# Nucleo.net
KiCad netlist of a schematic drawn in Altium Designer
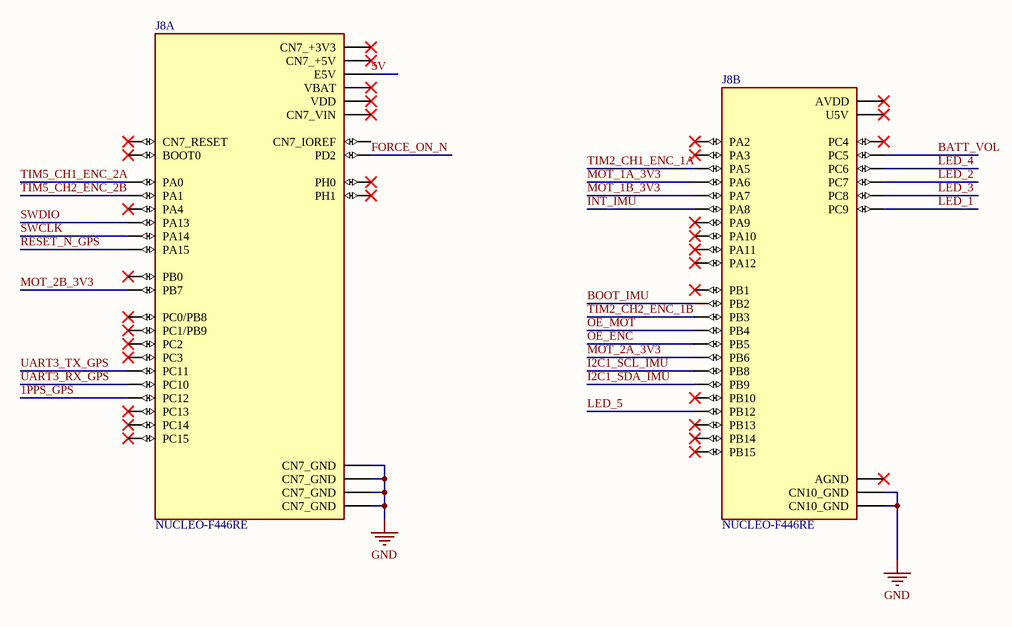
[diagram p0: Nucleo.SchDoc]

(export (version "E")
  (design (tool "Eeschema 10.0.6"))
  (components
    (comp (ref "J8")
      (value "NUCLEO-F446RE")
      (footprint "swarm_crawler_pcb:MODULE_NUCLEO-F446RE")
      (libsource (lib "swarm_crawler_sch") (part "NUCLEO-F446RE"))
    )
  )
  (nets
    (net (code "1") (name "/1PPS_GPS") (class "Default")
      (node (ref "J8") (pin "CN7_3") (pinfunction "PC12_CN7_3") (pintype "bidirectional"))
    )
    (net (code "2") (name "/5V") (class "Default")
      (node (ref "J8") (pin "CN7_6") (pinfunction "E5V_CN7_6") (pintype "power_in"))
    )
    (net (code "3") (name "/BATT_VOL") (class "Default")
      (node (ref "J8") (pin "CN10_6") (pinfunction "PC5_CN10_6") (pintype "bidirectional"))
    )
    (net (code "4") (name "/BOOT_IMU") (class "Default")
      (node (ref "J8") (pin "CN10_22") (pinfunction "PB2_CN10_22") (pintype "bidirectional"))
    )
    (net (code "5") (name "/FORCE_ON_N") (class "Default")
      (node (ref "J8") (pin "CN7_4") (pinfunction "PD2_CN7_4") (pintype "bidirectional"))
    )
    (net (code "6") (name "/I2C1_SCL_IMU") (class "Default")
      (node (ref "J8") (pin "CN10_3") (pinfunction "PB8_CN10_3") (pintype "bidirectional"))
    )
    (net (code "7") (name "/I2C1_SDA_IMU") (class "Default")
      (node (ref "J8") (pin "CN10_5") (pinfunction "PB9_CN10_5") (pintype "bidirectional"))
    )
    (net (code "8") (name "/INT_IMU") (class "Default")
      (node (ref "J8") (pin "CN10_23") (pinfunction "PA8_CN10_23") (pintype "bidirectional"))
    )
    (net (code "9") (name "/LED_1") (class "Default")
      (node (ref "J8") (pin "CN10_1") (pinfunction "PC9_CN10_1") (pintype "bidirectional"))
    )
    (net (code "10") (name "/LED_2") (class "Default")
      (node (ref "J8") (pin "CN10_19") (pinfunction "PC7_CN10_19") (pintype "bidirectional"))
    )
    (net (code "11") (name "/LED_3") (class "Default")
      (node (ref "J8") (pin "CN10_2") (pinfunction "PC8_CN10_2") (pintype "bidirectional"))
    )
    (net (code "12") (name "/LED_4") (class "Default")
      (node (ref "J8") (pin "CN10_4") (pinfunction "PC6_CN10_4") (pintype "bidirectional"))
    )
    (net (code "13") (name "/LED_5") (class "Default")
      (node (ref "J8") (pin "CN10_16") (pinfunction "PB12_CN10_16") (pintype "bidirectional"))
    )
    (net (code "14") (name "/MOT_1A_3V3") (class "Default")
      (node (ref "J8") (pin "CN10_13") (pinfunction "PA6_CN10_13") (pintype "bidirectional"))
    )
    (net (code "15") (name "/MOT_1B_3V3") (class "Default")
      (node (ref "J8") (pin "CN10_15") (pinfunction "PA7_CN10_15") (pintype "bidirectional"))
    )
    (net (code "16") (name "/MOT_2A_3V3") (class "Default")
      (node (ref "J8") (pin "CN10_17") (pinfunction "PB6_CN10_17") (pintype "bidirectional"))
    )
    (net (code "17") (name "/MOT_2B_3V3") (class "Default")
      (node (ref "J8") (pin "CN7_21") (pinfunction "PB7_CN7_21") (pintype "bidirectional"))
    )
    (net (code "18") (name "/OE_ENC") (class "Default")
      (node (ref "J8") (pin "CN10_29") (pinfunction "PB5_CN10_29") (pintype "bidirectional"))
    )
    (net (code "19") (name "/OE_MOT") (class "Default")
      (node (ref "J8") (pin "CN10_27") (pinfunction "PB4_CN10_27") (pintype "bidirectional"))
    )
    (net (code "20") (name "/RESET_N_GPS") (class "Default")
      (node (ref "J8") (pin "CN7_17") (pinfunction "PA15_CN7_17") (pintype "bidirectional"))
    )
    (net (code "21") (name "/SWCLK") (class "Default")
      (node (ref "J8") (pin "CN7_15") (pinfunction "PA14_CN7_15") (pintype "bidirectional"))
    )
    (net (code "22") (name "/SWDIO") (class "Default")
      (node (ref "J8") (pin "CN7_13") (pinfunction "PA13_CN7_13") (pintype "bidirectional"))
    )
    (net (code "23") (name "/TIM2_CH1_ENC_1A") (class "Default")
      (node (ref "J8") (pin "CN10_11") (pinfunction "PA5_CN10_11") (pintype "bidirectional"))
    )
    (net (code "24") (name "/TIM2_CH2_ENC_1B") (class "Default")
      (node (ref "J8") (pin "CN10_31") (pinfunction "PB3_CN10_31") (pintype "bidirectional"))
    )
    (net (code "25") (name "/TIM5_CH1_ENC_2A") (class "Default")
      (node (ref "J8") (pin "CN7_28") (pinfunction "PA0_CN7_28") (pintype "bidirectional"))
    )
    (net (code "26") (name "/TIM5_CH2_ENC_2B") (class "Default")
      (node (ref "J8") (pin "CN7_30") (pinfunction "PA1_CN7_30") (pintype "bidirectional"))
    )
    (net (code "27") (name "/UART3_RX_GPS") (class "Default")
      (node (ref "J8") (pin "CN7_1") (pinfunction "PC10_CN7_1") (pintype "bidirectional"))
    )
    (net (code "28") (name "/UART3_TX_GPS") (class "Default")
      (node (ref "J8") (pin "CN7_2") (pinfunction "PC11_CN7_2") (pintype "bidirectional"))
    )
    (net (code "29") (name "GND") (class "Default")
      (node (ref "J8") (pin "CN10_20") (pinfunction "CN10_GND_CN10_20") (pintype "power_in"))
      (node (ref "J8") (pin "CN10_9") (pinfunction "CN10_GND_CN10_9") (pintype "power_in"))
      (node (ref "J8") (pin "CN7_19") (pinfunction "CN7_GND_CN7_19") (pintype "power_in"))
      (node (ref "J8") (pin "CN7_20") (pinfunction "CN7_GND_CN7_20") (pintype "power_in"))
      (node (ref "J8") (pin "CN7_22") (pinfunction "CN7_GND_CN7_22") (pintype "power_in"))
      (node (ref "J8") (pin "CN7_8") (pinfunction "CN7_GND_CN7_8") (pintype "power_in"))
    )
    (net (code "30") (name "unconnected-(J8A-BOOT0-PadCN7_7)") (class "Default")
      (node (ref "J8") (pin "CN7_7") (pinfunction "BOOT0_CN7_7") (pintype "bidirectional+no_connect"))
    )
    (net (code "31") (name "unconnected-(J8A-CN7_+3V3-PadCN7_16)") (class "Default")
      (node (ref "J8") (pin "CN7_16") (pinfunction "CN7_+3V3_CN7_16") (pintype "power_in+no_connect"))
    )
    (net (code "32") (name "unconnected-(J8A-CN7_+5V-PadCN7_18)") (class "Default")
      (node (ref "J8") (pin "CN7_18") (pinfunction "CN7_+5V_CN7_18") (pintype "power_in+no_connect"))
    )
    (net (code "33") (name "unconnected-(J8A-CN7_IOREF-PadCN7_12)") (class "Default")
      (node (ref "J8") (pin "CN7_12") (pinfunction "CN7_IOREF_CN7_12") (pintype "bidirectional"))
    )
    (net (code "34") (name "unconnected-(J8A-CN7_RESET-PadCN7_14)") (class "Default")
      (node (ref "J8") (pin "CN7_14") (pinfunction "CN7_RESET_CN7_14") (pintype "bidirectional+no_connect"))
    )
    (net (code "35") (name "unconnected-(J8A-CN7_VIN-PadCN7_24)") (class "Default")
      (node (ref "J8") (pin "CN7_24") (pinfunction "CN7_VIN_CN7_24") (pintype "power_in+no_connect"))
    )
    (net (code "36") (name "unconnected-(J8A-PA4-PadCN7_32)") (class "Default")
      (node (ref "J8") (pin "CN7_32") (pinfunction "PA4_CN7_32") (pintype "bidirectional+no_connect"))
    )
    (net (code "37") (name "unconnected-(J8A-PB0-PadCN7_34)") (class "Default")
      (node (ref "J8") (pin "CN7_34") (pinfunction "PB0_CN7_34") (pintype "bidirectional+no_connect"))
    )
    (net (code "38") (name "unconnected-(J8A-PC0{slash}PB8-PadCN7_38)") (class "Default")
      (node (ref "J8") (pin "CN7_38") (pinfunction "PC0/PB8_CN7_38") (pintype "bidirectional+no_connect"))
    )
    (net (code "39") (name "unconnected-(J8A-PC1{slash}PB9-PadCN7_36)") (class "Default")
      (node (ref "J8") (pin "CN7_36") (pinfunction "PC1/PB9_CN7_36") (pintype "bidirectional+no_connect"))
    )
    (net (code "40") (name "unconnected-(J8A-PC2-PadCN7_35)") (class "Default")
      (node (ref "J8") (pin "CN7_35") (pinfunction "PC2_CN7_35") (pintype "bidirectional+no_connect"))
    )
    (net (code "41") (name "unconnected-(J8A-PC3-PadCN7_37)") (class "Default")
      (node (ref "J8") (pin "CN7_37") (pinfunction "PC3_CN7_37") (pintype "bidirectional+no_connect"))
    )
    (net (code "42") (name "unconnected-(J8A-PC13-PadCN7_23)") (class "Default")
      (node (ref "J8") (pin "CN7_23") (pinfunction "PC13_CN7_23") (pintype "bidirectional+no_connect"))
    )
    (net (code "43") (name "unconnected-(J8A-PC14-PadCN7_25)") (class "Default")
      (node (ref "J8") (pin "CN7_25") (pinfunction "PC14_CN7_25") (pintype "bidirectional+no_connect"))
    )
    (net (code "44") (name "unconnected-(J8A-PC15-PadCN7_27)") (class "Default")
      (node (ref "J8") (pin "CN7_27") (pinfunction "PC15_CN7_27") (pintype "bidirectional+no_connect"))
    )
    (net (code "45") (name "unconnected-(J8A-PH0-PadCN7_29)") (class "Default")
      (node (ref "J8") (pin "CN7_29") (pinfunction "PH0_CN7_29") (pintype "bidirectional+no_connect"))
    )
    (net (code "46") (name "unconnected-(J8A-PH1-PadCN7_31)") (class "Default")
      (node (ref "J8") (pin "CN7_31") (pinfunction "PH1_CN7_31") (pintype "bidirectional+no_connect"))
    )
    (net (code "47") (name "unconnected-(J8A-VBAT-PadCN7_33)") (class "Default")
      (node (ref "J8") (pin "CN7_33") (pinfunction "VBAT_CN7_33") (pintype "power_in+no_connect"))
    )
    (net (code "48") (name "unconnected-(J8A-VDD-PadCN7_5)") (class "Default")
      (node (ref "J8") (pin "CN7_5") (pinfunction "VDD_CN7_5") (pintype "power_in+no_connect"))
    )
    (net (code "49") (name "unconnected-(J8B-AGND-PadCN10_32)") (class "Default")
      (node (ref "J8") (pin "CN10_32") (pinfunction "AGND_CN10_32") (pintype "power_in+no_connect"))
    )
    (net (code "50") (name "unconnected-(J8B-AVDD-PadCN10_7)") (class "Default")
      (node (ref "J8") (pin "CN10_7") (pinfunction "AVDD_CN10_7") (pintype "power_in+no_connect"))
    )
    (net (code "51") (name "unconnected-(J8B-PA2-PadCN10_35)") (class "Default")
      (node (ref "J8") (pin "CN10_35") (pinfunction "PA2_CN10_35") (pintype "bidirectional+no_connect"))
    )
    (net (code "52") (name "unconnected-(J8B-PA3-PadCN10_37)") (class "Default")
      (node (ref "J8") (pin "CN10_37") (pinfunction "PA3_CN10_37") (pintype "bidirectional+no_connect"))
    )
    (net (code "53") (name "unconnected-(J8B-PA9-PadCN10_21)") (class "Default")
      (node (ref "J8") (pin "CN10_21") (pinfunction "PA9_CN10_21") (pintype "bidirectional+no_connect"))
    )
    (net (code "54") (name "unconnected-(J8B-PA10-PadCN10_33)") (class "Default")
      (node (ref "J8") (pin "CN10_33") (pinfunction "PA10_CN10_33") (pintype "bidirectional+no_connect"))
    )
    (net (code "55") (name "unconnected-(J8B-PA11-PadCN10_14)") (class "Default")
      (node (ref "J8") (pin "CN10_14") (pinfunction "PA11_CN10_14") (pintype "bidirectional+no_connect"))
    )
    (net (code "56") (name "unconnected-(J8B-PA12-PadCN10_12)") (class "Default")
      (node (ref "J8") (pin "CN10_12") (pinfunction "PA12_CN10_12") (pintype "bidirectional+no_connect"))
    )
    (net (code "57") (name "unconnected-(J8B-PB1-PadCN10_24)") (class "Default")
      (node (ref "J8") (pin "CN10_24") (pinfunction "PB1_CN10_24") (pintype "bidirectional+no_connect"))
    )
    (net (code "58") (name "unconnected-(J8B-PB10-PadCN10_25)") (class "Default")
      (node (ref "J8") (pin "CN10_25") (pinfunction "PB10_CN10_25") (pintype "bidirectional+no_connect"))
    )
    (net (code "59") (name "unconnected-(J8B-PB13-PadCN10_30)") (class "Default")
      (node (ref "J8") (pin "CN10_30") (pinfunction "PB13_CN10_30") (pintype "bidirectional+no_connect"))
    )
    (net (code "60") (name "unconnected-(J8B-PB14-PadCN10_28)") (class "Default")
      (node (ref "J8") (pin "CN10_28") (pinfunction "PB14_CN10_28") (pintype "bidirectional+no_connect"))
    )
    (net (code "61") (name "unconnected-(J8B-PB15-PadCN10_26)") (class "Default")
      (node (ref "J8") (pin "CN10_26") (pinfunction "PB15_CN10_26") (pintype "bidirectional+no_connect"))
    )
    (net (code "62") (name "unconnected-(J8B-PC4-PadCN10_34)") (class "Default")
      (node (ref "J8") (pin "CN10_34") (pinfunction "PC4_CN10_34") (pintype "bidirectional+no_connect"))
    )
    (net (code "63") (name "unconnected-(J8B-U5V-PadCN10_8)") (class "Default")
      (node (ref "J8") (pin "CN10_8") (pinfunction "U5V_CN10_8") (pintype "power_in+no_connect"))
    )
  )
)
